# INT_CONN.net
KiCad netlist of a schematic drawn in Altium Designer
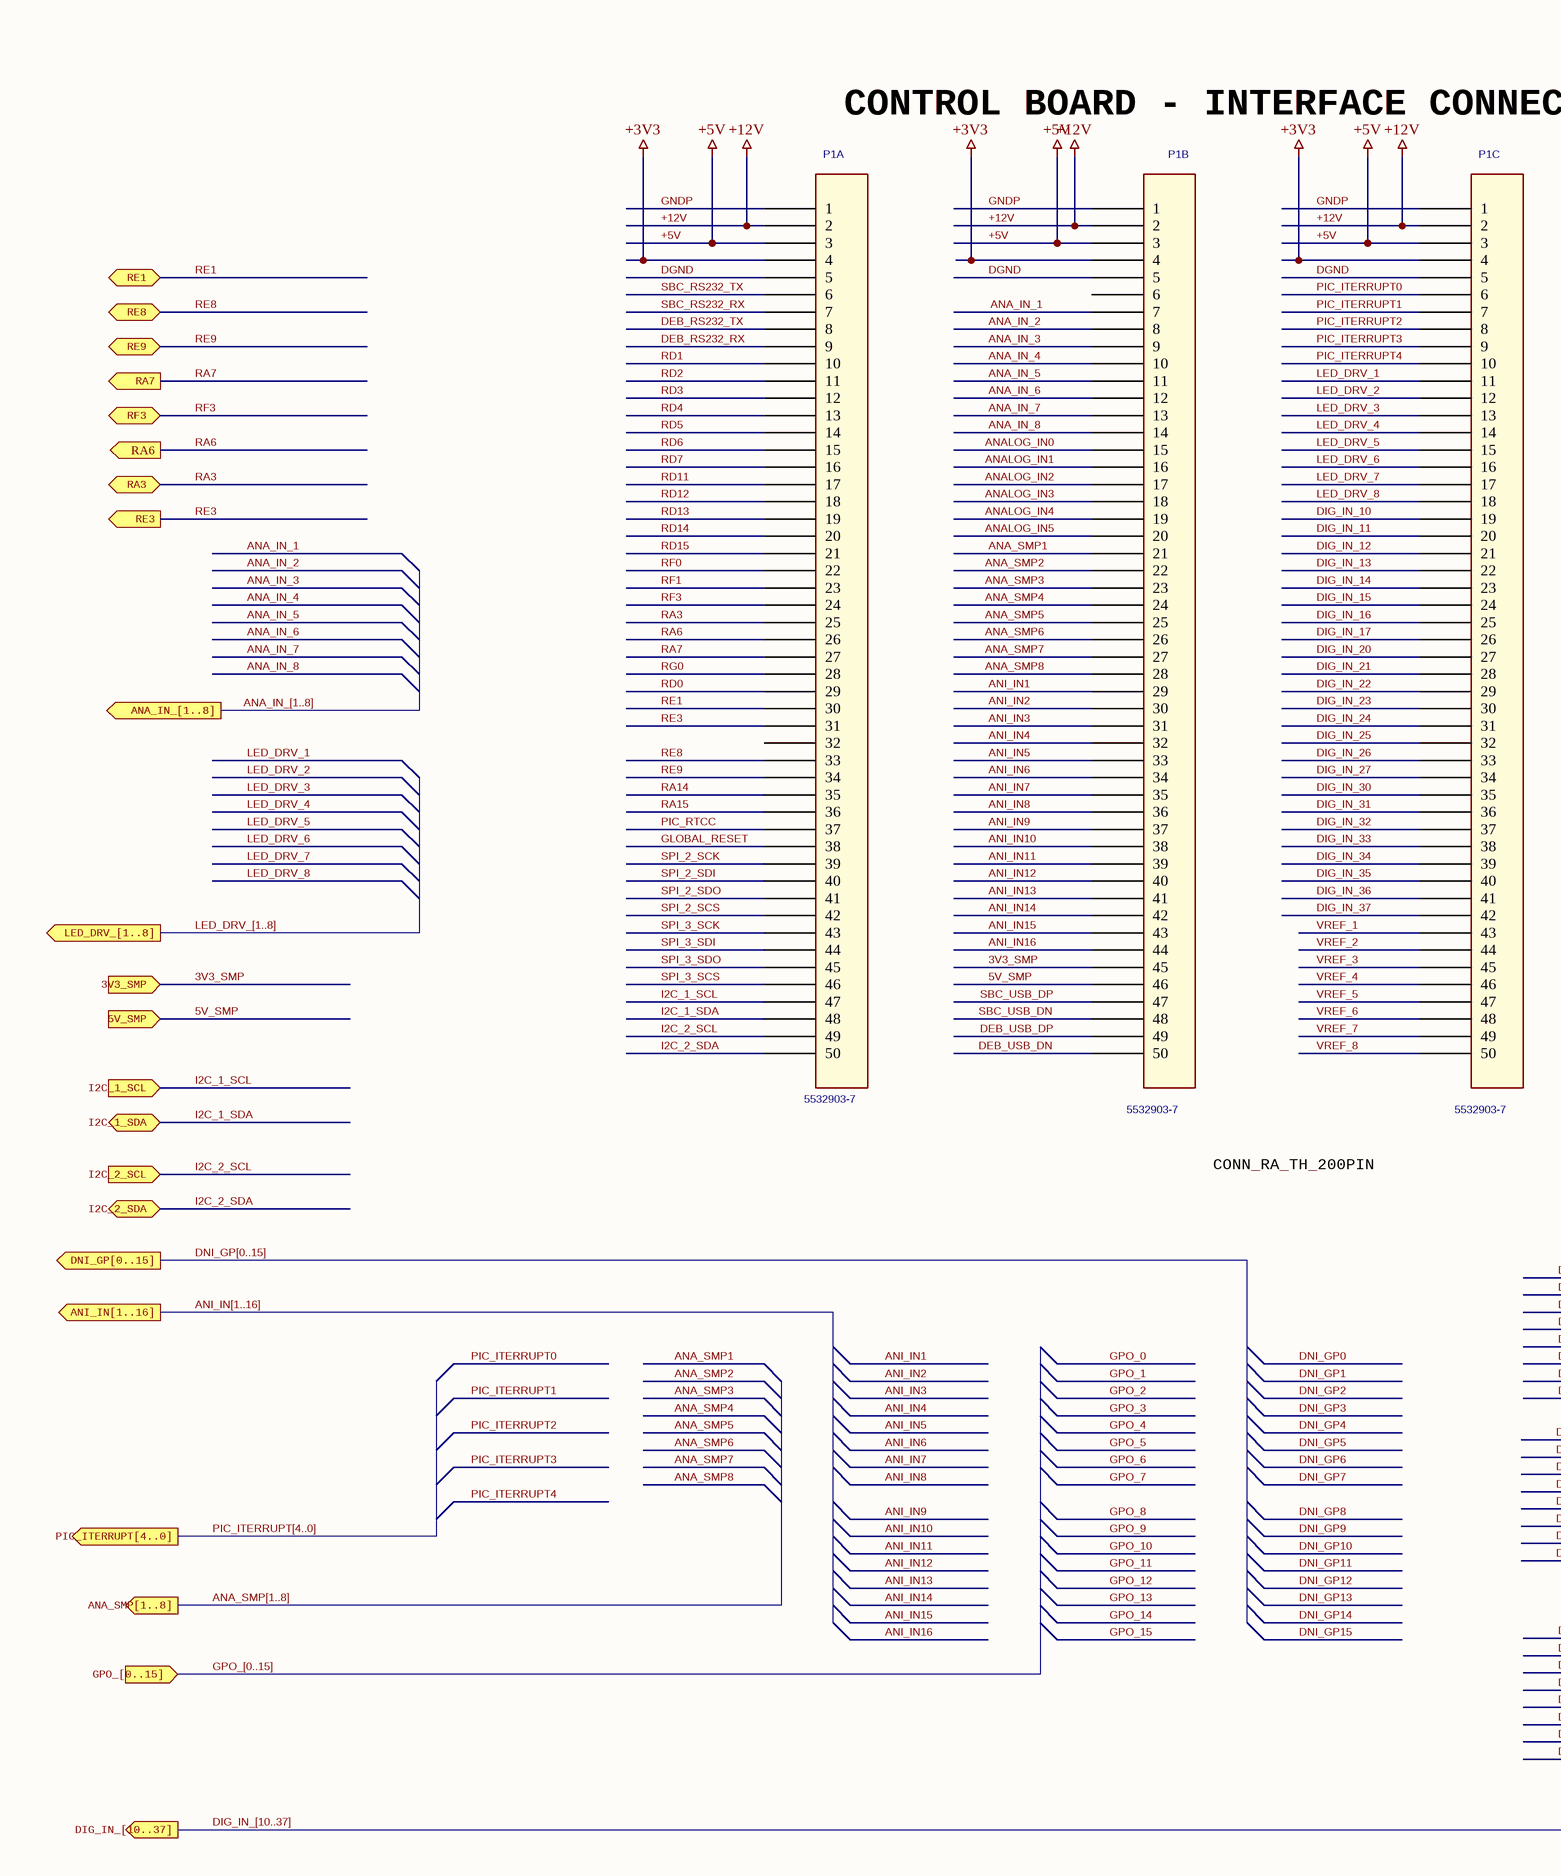
[diagram p0: INT_CONN.SchDoc, left]
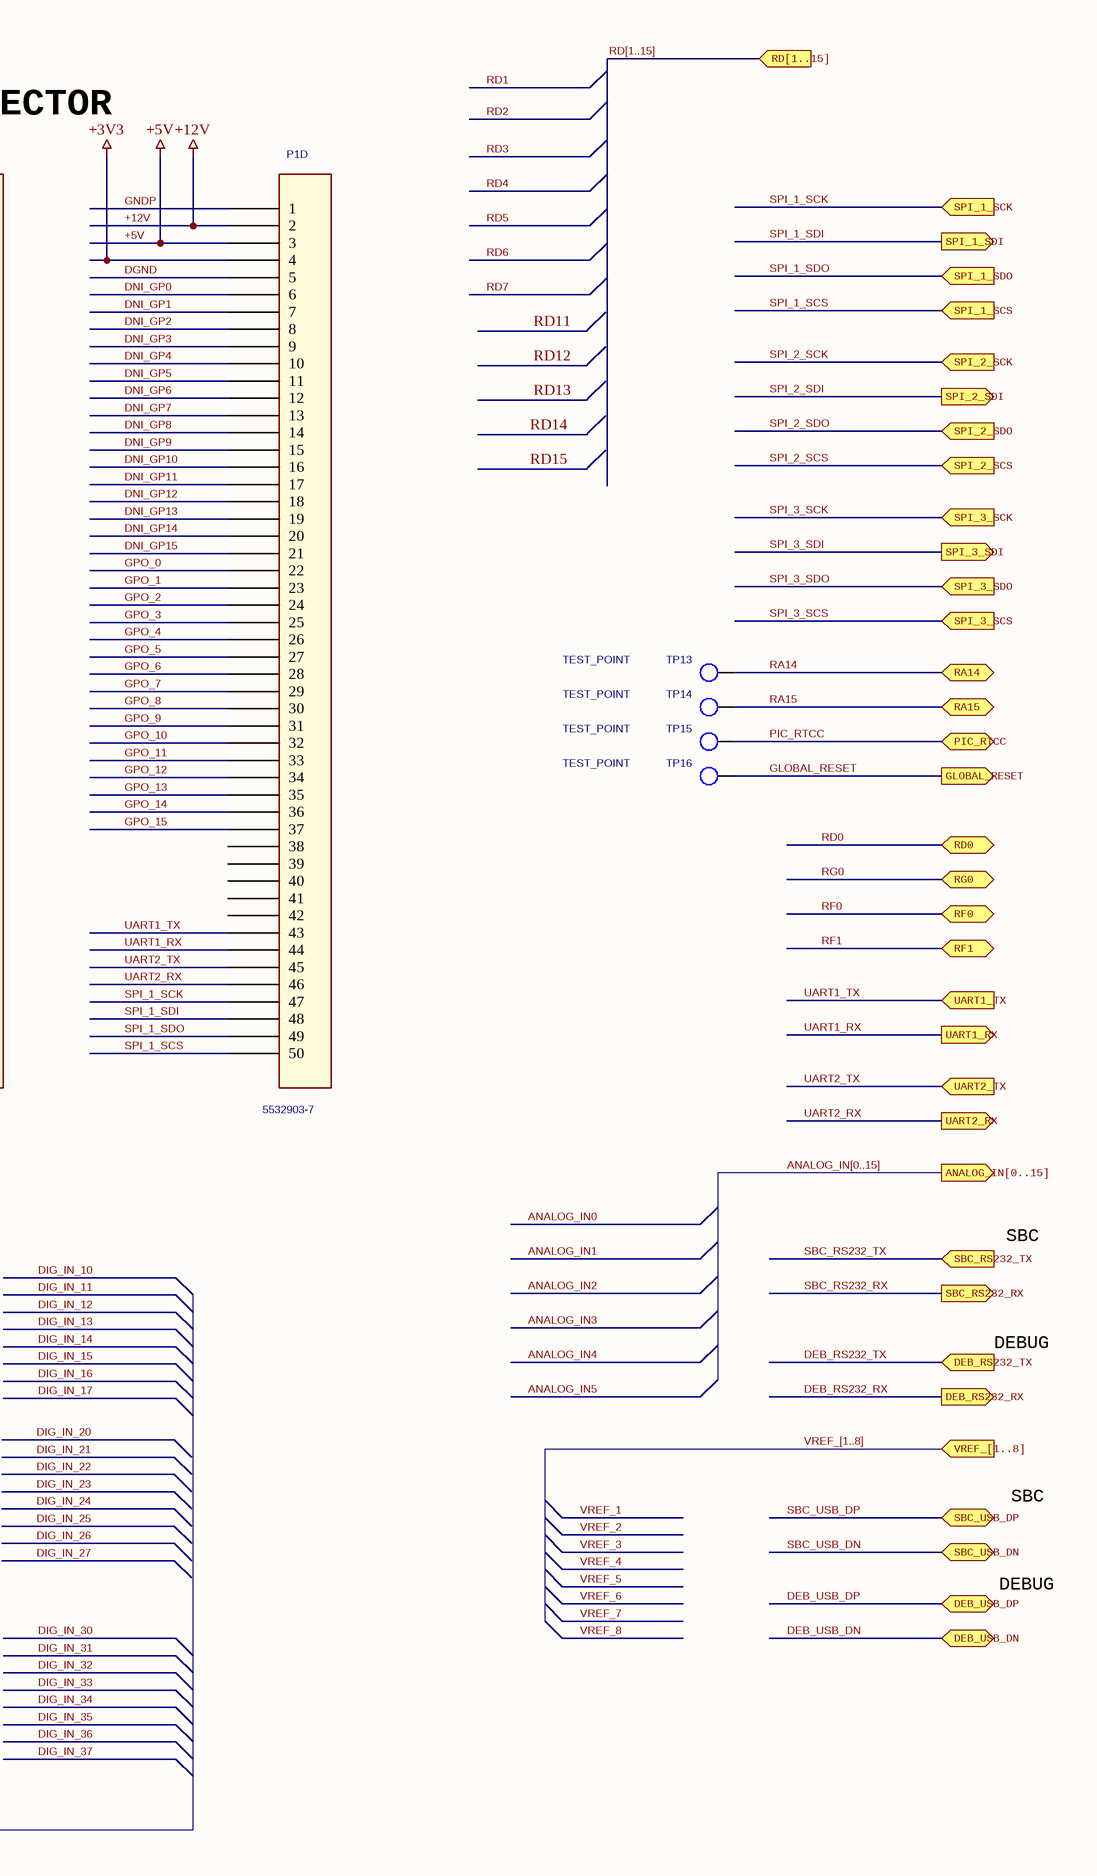
[diagram p1: INT_CONN.SchDoc, right]

(export (version "E")
  (design (tool "Eeschema 10.0.6"))
  (components
    (comp (ref "P1")
      (value "5532903-7")
      (footprint "TH_4X50_100mil")
      (libsource (lib "*") (part "CONN_RA_TH_200PIN"))
    )
    (comp (ref "TP13")
      (value "TEST_POINT")
      (footprint "TH_1mm")
      (libsource (lib "*") (part "T POINT R_Dup1"))
    )
    (comp (ref "TP14")
      (value "TEST_POINT")
      (footprint "TH_1mm")
      (libsource (lib "*") (part "T POINT R_Dup1"))
    )
    (comp (ref "TP15")
      (value "TEST_POINT")
      (footprint "TH_1mm")
      (libsource (lib "*") (part "T POINT R_Dup1"))
    )
    (comp (ref "TP16")
      (value "TEST_POINT")
      (footprint "TH_1mm")
      (libsource (lib "*") (part "T POINT R_Dup1"))
    )
  )
  (nets
    (net (code "18") (name "+3V3") (class "Default")
      (node (ref "P1") (pin "4A") (pinfunction "4_4A") (pintype "passive"))
      (node (ref "P1") (pin "4B") (pinfunction "4_4B") (pintype "passive"))
      (node (ref "P1") (pin "4C") (pinfunction "4_4C") (pintype "passive"))
      (node (ref "P1") (pin "4D") (pinfunction "4_4D") (pintype "passive"))
    )
    (net (code "19") (name "+5V") (class "Default")
      (node (ref "P1") (pin "3A") (pinfunction "3_3A") (pintype "passive"))
      (node (ref "P1") (pin "3B") (pinfunction "3_3B") (pintype "passive"))
      (node (ref "P1") (pin "3C") (pinfunction "3_3C") (pintype "passive"))
      (node (ref "P1") (pin "3D") (pinfunction "3_3D") (pintype "passive"))
    )
    (net (code "20") (name "+12V") (class "Default")
      (node (ref "P1") (pin "2A") (pinfunction "2_2A") (pintype "passive"))
      (node (ref "P1") (pin "2B") (pinfunction "2_2B") (pintype "passive"))
      (node (ref "P1") (pin "2C") (pinfunction "2_2C") (pintype "passive"))
      (node (ref "P1") (pin "2D") (pinfunction "2_2D") (pintype "passive"))
    )
    (net (code "21") (name "/3V3_SMP") (class "Default")
      (node (ref "P1") (pin "45B") (pinfunction "45_45B") (pintype "passive"))
    )
    (net (code "22") (name "/5V_SMP") (class "Default")
      (node (ref "P1") (pin "46B") (pinfunction "46_46B") (pintype "passive"))
    )
    (net (code "23") (name "/ANALOG_IN0") (class "Default")
      (node (ref "P1") (pin "15B") (pinfunction "15_15B") (pintype "passive"))
    )
    (net (code "24") (name "/ANALOG_IN1") (class "Default")
      (node (ref "P1") (pin "16B") (pinfunction "16_16B") (pintype "passive"))
    )
    (net (code "25") (name "/ANALOG_IN2") (class "Default")
      (node (ref "P1") (pin "17B") (pinfunction "17_17B") (pintype "passive"))
    )
    (net (code "26") (name "/ANALOG_IN3") (class "Default")
      (node (ref "P1") (pin "18B") (pinfunction "18_18B") (pintype "passive"))
    )
    (net (code "27") (name "/ANALOG_IN4") (class "Default")
      (node (ref "P1") (pin "19B") (pinfunction "19_19B") (pintype "passive"))
    )
    (net (code "28") (name "/ANALOG_IN5") (class "Default")
      (node (ref "P1") (pin "20B") (pinfunction "20_20B") (pintype "passive"))
    )
    (net (code "30") (name "/ANA_IN_1") (class "Default")
      (node (ref "P1") (pin "7B") (pinfunction "7_7B") (pintype "passive"))
    )
    (net (code "31") (name "/ANA_IN_2") (class "Default")
      (node (ref "P1") (pin "8B") (pinfunction "8_8B") (pintype "passive"))
    )
    (net (code "32") (name "/ANA_IN_3") (class "Default")
      (node (ref "P1") (pin "9B") (pinfunction "9_9B") (pintype "passive"))
    )
    (net (code "33") (name "/ANA_IN_4") (class "Default")
      (node (ref "P1") (pin "10B") (pinfunction "10_10B") (pintype "passive"))
    )
    (net (code "34") (name "/ANA_IN_5") (class "Default")
      (node (ref "P1") (pin "11B") (pinfunction "11_11B") (pintype "passive"))
    )
    (net (code "35") (name "/ANA_IN_6") (class "Default")
      (node (ref "P1") (pin "12B") (pinfunction "12_12B") (pintype "passive"))
    )
    (net (code "36") (name "/ANA_IN_7") (class "Default")
      (node (ref "P1") (pin "13B") (pinfunction "13_13B") (pintype "passive"))
    )
    (net (code "37") (name "/ANA_IN_8") (class "Default")
      (node (ref "P1") (pin "14B") (pinfunction "14_14B") (pintype "passive"))
    )
    (net (code "39") (name "/ANA_SMP1") (class "Default")
      (node (ref "P1") (pin "21B") (pinfunction "21_21B") (pintype "passive"))
    )
    (net (code "40") (name "/ANA_SMP2") (class "Default")
      (node (ref "P1") (pin "22B") (pinfunction "22_22B") (pintype "passive"))
    )
    (net (code "41") (name "/ANA_SMP3") (class "Default")
      (node (ref "P1") (pin "23B") (pinfunction "23_23B") (pintype "passive"))
    )
    (net (code "42") (name "/ANA_SMP4") (class "Default")
      (node (ref "P1") (pin "24B") (pinfunction "24_24B") (pintype "passive"))
    )
    (net (code "43") (name "/ANA_SMP5") (class "Default")
      (node (ref "P1") (pin "25B") (pinfunction "25_25B") (pintype "passive"))
    )
    (net (code "44") (name "/ANA_SMP6") (class "Default")
      (node (ref "P1") (pin "26B") (pinfunction "26_26B") (pintype "passive"))
    )
    (net (code "45") (name "/ANA_SMP7") (class "Default")
      (node (ref "P1") (pin "27B") (pinfunction "27_27B") (pintype "passive"))
    )
    (net (code "46") (name "/ANA_SMP8") (class "Default")
      (node (ref "P1") (pin "28B") (pinfunction "28_28B") (pintype "passive"))
    )
    (net (code "48") (name "/ANI_IN1") (class "Default")
      (node (ref "P1") (pin "29B") (pinfunction "29_29B") (pintype "passive"))
    )
    (net (code "49") (name "/ANI_IN2") (class "Default")
      (node (ref "P1") (pin "30B") (pinfunction "30_30B") (pintype "passive"))
    )
    (net (code "50") (name "/ANI_IN3") (class "Default")
      (node (ref "P1") (pin "31B") (pinfunction "31_31B") (pintype "passive"))
    )
    (net (code "51") (name "/ANI_IN4") (class "Default")
      (node (ref "P1") (pin "32B") (pinfunction "32_32B") (pintype "passive"))
    )
    (net (code "52") (name "/ANI_IN5") (class "Default")
      (node (ref "P1") (pin "33B") (pinfunction "33_33B") (pintype "passive"))
    )
    (net (code "53") (name "/ANI_IN6") (class "Default")
      (node (ref "P1") (pin "34B") (pinfunction "34_34B") (pintype "passive"))
    )
    (net (code "54") (name "/ANI_IN7") (class "Default")
      (node (ref "P1") (pin "35B") (pinfunction "35_35B") (pintype "passive"))
    )
    (net (code "55") (name "/ANI_IN8") (class "Default")
      (node (ref "P1") (pin "36B") (pinfunction "36_36B") (pintype "passive"))
    )
    (net (code "56") (name "/ANI_IN9") (class "Default")
      (node (ref "P1") (pin "37B") (pinfunction "37_37B") (pintype "passive"))
    )
    (net (code "57") (name "/ANI_IN10") (class "Default")
      (node (ref "P1") (pin "38B") (pinfunction "38_38B") (pintype "passive"))
    )
    (net (code "58") (name "/ANI_IN11") (class "Default")
      (node (ref "P1") (pin "39B") (pinfunction "39_39B") (pintype "passive"))
    )
    (net (code "59") (name "/ANI_IN12") (class "Default")
      (node (ref "P1") (pin "40B") (pinfunction "40_40B") (pintype "passive"))
    )
    (net (code "60") (name "/ANI_IN13") (class "Default")
      (node (ref "P1") (pin "41B") (pinfunction "41_41B") (pintype "passive"))
    )
    (net (code "61") (name "/ANI_IN14") (class "Default")
      (node (ref "P1") (pin "42B") (pinfunction "42_42B") (pintype "passive"))
    )
    (net (code "62") (name "/ANI_IN15") (class "Default")
      (node (ref "P1") (pin "43B") (pinfunction "43_43B") (pintype "passive"))
    )
    (net (code "63") (name "/ANI_IN16") (class "Default")
      (node (ref "P1") (pin "44B") (pinfunction "44_44B") (pintype "passive"))
    )
    (net (code "65") (name "/DEB_RS232_RX") (class "Default")
      (node (ref "P1") (pin "9A") (pinfunction "9_9A") (pintype "passive"))
    )
    (net (code "66") (name "/DEB_RS232_TX") (class "Default")
      (node (ref "P1") (pin "8A") (pinfunction "8_8A") (pintype "passive"))
    )
    (net (code "67") (name "/DEB_USB_DN") (class "Default")
      (node (ref "P1") (pin "50B") (pinfunction "50_50B") (pintype "passive"))
    )
    (net (code "68") (name "/DEB_USB_DP") (class "Default")
      (node (ref "P1") (pin "49B") (pinfunction "49_49B") (pintype "passive"))
    )
    (net (code "69") (name "/DGND") (class "Default")
      (node (ref "P1") (pin "5A") (pinfunction "5_5A") (pintype "passive"))
      (node (ref "P1") (pin "5B") (pinfunction "5_5B") (pintype "passive"))
      (node (ref "P1") (pin "5C") (pinfunction "5_5C") (pintype "passive"))
      (node (ref "P1") (pin "5D") (pinfunction "5_5D") (pintype "passive"))
    )
    (net (code "70") (name "/DIG_IN_10") (class "Default")
      (node (ref "P1") (pin "19C") (pinfunction "19_19C") (pintype "passive"))
    )
    (net (code "71") (name "/DIG_IN_11") (class "Default")
      (node (ref "P1") (pin "20C") (pinfunction "20_20C") (pintype "passive"))
    )
    (net (code "72") (name "/DIG_IN_12") (class "Default")
      (node (ref "P1") (pin "21C") (pinfunction "21_21C") (pintype "passive"))
    )
    (net (code "73") (name "/DIG_IN_13") (class "Default")
      (node (ref "P1") (pin "22C") (pinfunction "22_22C") (pintype "passive"))
    )
    (net (code "74") (name "/DIG_IN_14") (class "Default")
      (node (ref "P1") (pin "23C") (pinfunction "23_23C") (pintype "passive"))
    )
    (net (code "75") (name "/DIG_IN_15") (class "Default")
      (node (ref "P1") (pin "24C") (pinfunction "24_24C") (pintype "passive"))
    )
    (net (code "76") (name "/DIG_IN_16") (class "Default")
      (node (ref "P1") (pin "25C") (pinfunction "25_25C") (pintype "passive"))
    )
    (net (code "77") (name "/DIG_IN_17") (class "Default")
      (node (ref "P1") (pin "26C") (pinfunction "26_26C") (pintype "passive"))
    )
    (net (code "78") (name "/DIG_IN_20") (class "Default")
      (node (ref "P1") (pin "27C") (pinfunction "27_27C") (pintype "passive"))
    )
    (net (code "79") (name "/DIG_IN_21") (class "Default")
      (node (ref "P1") (pin "28C") (pinfunction "28_28C") (pintype "passive"))
    )
    (net (code "80") (name "/DIG_IN_22") (class "Default")
      (node (ref "P1") (pin "29C") (pinfunction "29_29C") (pintype "passive"))
    )
    (net (code "81") (name "/DIG_IN_23") (class "Default")
      (node (ref "P1") (pin "30C") (pinfunction "30_30C") (pintype "passive"))
    )
    (net (code "82") (name "/DIG_IN_24") (class "Default")
      (node (ref "P1") (pin "31C") (pinfunction "31_31C") (pintype "passive"))
    )
    (net (code "83") (name "/DIG_IN_25") (class "Default")
      (node (ref "P1") (pin "32C") (pinfunction "32_32C") (pintype "passive"))
    )
    (net (code "84") (name "/DIG_IN_26") (class "Default")
      (node (ref "P1") (pin "33C") (pinfunction "33_33C") (pintype "passive"))
    )
    (net (code "85") (name "/DIG_IN_27") (class "Default")
      (node (ref "P1") (pin "34C") (pinfunction "34_34C") (pintype "passive"))
    )
    (net (code "86") (name "/DIG_IN_30") (class "Default")
      (node (ref "P1") (pin "35C") (pinfunction "35_35C") (pintype "passive"))
    )
    (net (code "87") (name "/DIG_IN_31") (class "Default")
      (node (ref "P1") (pin "36C") (pinfunction "36_36C") (pintype "passive"))
    )
    (net (code "88") (name "/DIG_IN_32") (class "Default")
      (node (ref "P1") (pin "37C") (pinfunction "37_37C") (pintype "passive"))
    )
    (net (code "89") (name "/DIG_IN_33") (class "Default")
      (node (ref "P1") (pin "38C") (pinfunction "38_38C") (pintype "passive"))
    )
    (net (code "90") (name "/DIG_IN_34") (class "Default")
      (node (ref "P1") (pin "39C") (pinfunction "39_39C") (pintype "passive"))
    )
    (net (code "91") (name "/DIG_IN_35") (class "Default")
      (node (ref "P1") (pin "40C") (pinfunction "40_40C") (pintype "passive"))
    )
    (net (code "92") (name "/DIG_IN_36") (class "Default")
      (node (ref "P1") (pin "41C") (pinfunction "41_41C") (pintype "passive"))
    )
    (net (code "93") (name "/DIG_IN_37") (class "Default")
      (node (ref "P1") (pin "42C") (pinfunction "42_42C") (pintype "passive"))
    )
    (net (code "95") (name "/DNI_GP0") (class "Default")
      (node (ref "P1") (pin "6D") (pinfunction "6_6D") (pintype "passive"))
    )
    (net (code "96") (name "/DNI_GP1") (class "Default")
      (node (ref "P1") (pin "7D") (pinfunction "7_7D") (pintype "passive"))
    )
    (net (code "97") (name "/DNI_GP2") (class "Default")
      (node (ref "P1") (pin "8D") (pinfunction "8_8D") (pintype "passive"))
    )
    (net (code "98") (name "/DNI_GP3") (class "Default")
      (node (ref "P1") (pin "9D") (pinfunction "9_9D") (pintype "passive"))
    )
    (net (code "99") (name "/DNI_GP4") (class "Default")
      (node (ref "P1") (pin "10D") (pinfunction "10_10D") (pintype "passive"))
    )
    (net (code "100") (name "/DNI_GP5") (class "Default")
      (node (ref "P1") (pin "11D") (pinfunction "11_11D") (pintype "passive"))
    )
    (net (code "101") (name "/DNI_GP6") (class "Default")
      (node (ref "P1") (pin "12D") (pinfunction "12_12D") (pintype "passive"))
    )
    (net (code "102") (name "/DNI_GP7") (class "Default")
      (node (ref "P1") (pin "13D") (pinfunction "13_13D") (pintype "passive"))
    )
    (net (code "103") (name "/DNI_GP8") (class "Default")
      (node (ref "P1") (pin "14D") (pinfunction "14_14D") (pintype "passive"))
    )
    (net (code "104") (name "/DNI_GP9") (class "Default")
      (node (ref "P1") (pin "15D") (pinfunction "15_15D") (pintype "passive"))
    )
    (net (code "105") (name "/DNI_GP10") (class "Default")
      (node (ref "P1") (pin "16D") (pinfunction "16_16D") (pintype "passive"))
    )
    (net (code "106") (name "/DNI_GP11") (class "Default")
      (node (ref "P1") (pin "17D") (pinfunction "17_17D") (pintype "passive"))
    )
    (net (code "107") (name "/DNI_GP12") (class "Default")
      (node (ref "P1") (pin "18D") (pinfunction "18_18D") (pintype "passive"))
    )
    (net (code "108") (name "/DNI_GP13") (class "Default")
      (node (ref "P1") (pin "19D") (pinfunction "19_19D") (pintype "passive"))
    )
    (net (code "109") (name "/DNI_GP14") (class "Default")
      (node (ref "P1") (pin "20D") (pinfunction "20_20D") (pintype "passive"))
    )
    (net (code "110") (name "/DNI_GP15") (class "Default")
      (node (ref "P1") (pin "21D") (pinfunction "21_21D") (pintype "passive"))
    )
    (net (code "112") (name "/GLOBAL_RESET") (class "Default")
      (node (ref "P1") (pin "38A") (pinfunction "38_38A") (pintype "passive"))
      (node (ref "TP16") (pin "1") (pinfunction "TP_1") (pintype "passive"))
    )
    (net (code "113") (name "/GNDP") (class "Default")
      (node (ref "P1") (pin "1A") (pinfunction "1_1A") (pintype "passive"))
      (node (ref "P1") (pin "1B") (pinfunction "1_1B") (pintype "passive"))
      (node (ref "P1") (pin "1C") (pinfunction "1_1C") (pintype "passive"))
      (node (ref "P1") (pin "1D") (pinfunction "1_1D") (pintype "passive"))
    )
    (net (code "114") (name "/GPO_0") (class "Default")
      (node (ref "P1") (pin "22D") (pinfunction "22_22D") (pintype "passive"))
    )
    (net (code "115") (name "/GPO_1") (class "Default")
      (node (ref "P1") (pin "23D") (pinfunction "23_23D") (pintype "passive"))
    )
    (net (code "116") (name "/GPO_2") (class "Default")
      (node (ref "P1") (pin "24D") (pinfunction "24_24D") (pintype "passive"))
    )
    (net (code "117") (name "/GPO_3") (class "Default")
      (node (ref "P1") (pin "25D") (pinfunction "25_25D") (pintype "passive"))
    )
    (net (code "118") (name "/GPO_4") (class "Default")
      (node (ref "P1") (pin "26D") (pinfunction "26_26D") (pintype "passive"))
    )
    (net (code "119") (name "/GPO_5") (class "Default")
      (node (ref "P1") (pin "27D") (pinfunction "27_27D") (pintype "passive"))
    )
    (net (code "120") (name "/GPO_6") (class "Default")
      (node (ref "P1") (pin "28D") (pinfunction "28_28D") (pintype "passive"))
    )
    (net (code "121") (name "/GPO_7") (class "Default")
      (node (ref "P1") (pin "29D") (pinfunction "29_29D") (pintype "passive"))
    )
    (net (code "122") (name "/GPO_8") (class "Default")
      (node (ref "P1") (pin "30D") (pinfunction "30_30D") (pintype "passive"))
    )
    (net (code "123") (name "/GPO_9") (class "Default")
      (node (ref "P1") (pin "31D") (pinfunction "31_31D") (pintype "passive"))
    )
    (net (code "124") (name "/GPO_10") (class "Default")
      (node (ref "P1") (pin "32D") (pinfunction "32_32D") (pintype "passive"))
    )
    (net (code "125") (name "/GPO_11") (class "Default")
      (node (ref "P1") (pin "33D") (pinfunction "33_33D") (pintype "passive"))
    )
    (net (code "126") (name "/GPO_12") (class "Default")
      (node (ref "P1") (pin "34D") (pinfunction "34_34D") (pintype "passive"))
    )
    (net (code "127") (name "/GPO_13") (class "Default")
      (node (ref "P1") (pin "35D") (pinfunction "35_35D") (pintype "passive"))
    )
    (net (code "128") (name "/GPO_14") (class "Default")
      (node (ref "P1") (pin "36D") (pinfunction "36_36D") (pintype "passive"))
    )
    (net (code "129") (name "/GPO_15") (class "Default")
      (node (ref "P1") (pin "37D") (pinfunction "37_37D") (pintype "passive"))
    )
    (net (code "131") (name "/I2C_1_SCL") (class "Default")
      (node (ref "P1") (pin "47A") (pinfunction "47_47A") (pintype "passive"))
    )
    (net (code "132") (name "/I2C_1_SDA") (class "Default")
      (node (ref "P1") (pin "48A") (pinfunction "48_48A") (pintype "passive"))
    )
    (net (code "133") (name "/I2C_2_SCL") (class "Default")
      (node (ref "P1") (pin "49A") (pinfunction "49_49A") (pintype "passive"))
    )
    (net (code "134") (name "/I2C_2_SDA") (class "Default")
      (node (ref "P1") (pin "50A") (pinfunction "50_50A") (pintype "passive"))
    )
    (net (code "135") (name "/LED_DRV_1") (class "Default")
      (node (ref "P1") (pin "11C") (pinfunction "11_11C") (pintype "passive"))
    )
    (net (code "136") (name "/LED_DRV_2") (class "Default")
      (node (ref "P1") (pin "12C") (pinfunction "12_12C") (pintype "passive"))
    )
    (net (code "137") (name "/LED_DRV_3") (class "Default")
      (node (ref "P1") (pin "13C") (pinfunction "13_13C") (pintype "passive"))
    )
    (net (code "138") (name "/LED_DRV_4") (class "Default")
      (node (ref "P1") (pin "14C") (pinfunction "14_14C") (pintype "passive"))
    )
    (net (code "139") (name "/LED_DRV_5") (class "Default")
      (node (ref "P1") (pin "15C") (pinfunction "15_15C") (pintype "passive"))
    )
    (net (code "140") (name "/LED_DRV_6") (class "Default")
      (node (ref "P1") (pin "16C") (pinfunction "16_16C") (pintype "passive"))
    )
    (net (code "141") (name "/LED_DRV_7") (class "Default")
      (node (ref "P1") (pin "17C") (pinfunction "17_17C") (pintype "passive"))
    )
    (net (code "142") (name "/LED_DRV_8") (class "Default")
      (node (ref "P1") (pin "18C") (pinfunction "18_18C") (pintype "passive"))
    )
    (net (code "144") (name "/PIC_ITERRUPT0") (class "Default")
      (node (ref "P1") (pin "6C") (pinfunction "6_6C") (pintype "passive"))
    )
    (net (code "145") (name "/PIC_ITERRUPT1") (class "Default")
      (node (ref "P1") (pin "7C") (pinfunction "7_7C") (pintype "passive"))
    )
    (net (code "146") (name "/PIC_ITERRUPT2") (class "Default")
      (node (ref "P1") (pin "8C") (pinfunction "8_8C") (pintype "passive"))
    )
    (net (code "147") (name "/PIC_ITERRUPT3") (class "Default")
      (node (ref "P1") (pin "9C") (pinfunction "9_9C") (pintype "passive"))
    )
    (net (code "148") (name "/PIC_ITERRUPT4") (class "Default")
      (node (ref "P1") (pin "10C") (pinfunction "10_10C") (pintype "passive"))
    )
    (net (code "150") (name "/PIC_RTCC") (class "Default")
      (node (ref "P1") (pin "37A") (pinfunction "37_37A") (pintype "passive"))
      (node (ref "TP15") (pin "1") (pinfunction "TP_1") (pintype "passive"))
    )
    (net (code "151") (name "/RA3") (class "Default")
      (node (ref "P1") (pin "25A") (pinfunction "25_25A") (pintype "passive"))
    )
    (net (code "152") (name "/RA6") (class "Default")
      (node (ref "P1") (pin "26A") (pinfunction "26_26A") (pintype "passive"))
    )
    (net (code "153") (name "/RA7") (class "Default")
      (node (ref "P1") (pin "27A") (pinfunction "27_27A") (pintype "passive"))
    )
    (net (code "154") (name "/RA14") (class "Default")
      (node (ref "P1") (pin "35A") (pinfunction "35_35A") (pintype "passive"))
      (node (ref "TP13") (pin "1") (pinfunction "TP_1") (pintype "passive"))
    )
    (net (code "155") (name "/RA15") (class "Default")
      (node (ref "P1") (pin "36A") (pinfunction "36_36A") (pintype "passive"))
      (node (ref "TP14") (pin "1") (pinfunction "TP_1") (pintype "passive"))
    )
    (net (code "156") (name "/RD0") (class "Default")
      (node (ref "P1") (pin "29A") (pinfunction "29_29A") (pintype "passive"))
    )
    (net (code "157") (name "/RD1") (class "Default")
      (node (ref "P1") (pin "10A") (pinfunction "10_10A") (pintype "passive"))
    )
    (net (code "158") (name "/RD2") (class "Default")
      (node (ref "P1") (pin "11A") (pinfunction "11_11A") (pintype "passive"))
    )
    (net (code "159") (name "/RD3") (class "Default")
      (node (ref "P1") (pin "12A") (pinfunction "12_12A") (pintype "passive"))
    )
    (net (code "160") (name "/RD4") (class "Default")
      (node (ref "P1") (pin "13A") (pinfunction "13_13A") (pintype "passive"))
    )
    (net (code "161") (name "/RD5") (class "Default")
      (node (ref "P1") (pin "14A") (pinfunction "14_14A") (pintype "passive"))
    )
    (net (code "162") (name "/RD6") (class "Default")
      (node (ref "P1") (pin "15A") (pinfunction "15_15A") (pintype "passive"))
    )
    (net (code "163") (name "/RD7") (class "Default")
      (node (ref "P1") (pin "16A") (pinfunction "16_16A") (pintype "passive"))
    )
    (net (code "164") (name "/RD11") (class "Default")
      (node (ref "P1") (pin "17A") (pinfunction "17_17A") (pintype "passive"))
    )
    (net (code "165") (name "/RD12") (class "Default")
      (node (ref "P1") (pin "18A") (pinfunction "18_18A") (pintype "passive"))
    )
    (net (code "166") (name "/RD13") (class "Default")
      (node (ref "P1") (pin "19A") (pinfunction "19_19A") (pintype "passive"))
    )
    (net (code "167") (name "/RD14") (class "Default")
      (node (ref "P1") (pin "20A") (pinfunction "20_20A") (pintype "passive"))
    )
    (net (code "168") (name "/RD15") (class "Default")
      (node (ref "P1") (pin "21A") (pinfunction "21_21A") (pintype "passive"))
    )
    (net (code "170") (name "/RE1") (class "Default")
      (node (ref "P1") (pin "30A") (pinfunction "30_30A") (pintype "passive"))
    )
    (net (code "171") (name "/RE3") (class "Default")
      (node (ref "P1") (pin "31A") (pinfunction "31_31A") (pintype "passive"))
    )
    (net (code "172") (name "/RE8") (class "Default")
      (node (ref "P1") (pin "33A") (pinfunction "33_33A") (pintype "passive"))
    )
    (net (code "173") (name "/RE9") (class "Default")
      (node (ref "P1") (pin "34A") (pinfunction "34_34A") (pintype "passive"))
    )
    (net (code "174") (name "/RF0") (class "Default")
      (node (ref "P1") (pin "22A") (pinfunction "22_22A") (pintype "passive"))
    )
    (net (code "175") (name "/RF1") (class "Default")
      (node (ref "P1") (pin "23A") (pinfunction "23_23A") (pintype "passive"))
    )
    (net (code "176") (name "/RF3") (class "Default")
      (node (ref "P1") (pin "24A") (pinfunction "24_24A") (pintype "passive"))
    )
    (net (code "177") (name "/RG0") (class "Default")
      (node (ref "P1") (pin "28A") (pinfunction "28_28A") (pintype "passive"))
    )
    (net (code "178") (name "/SBC_RS232_RX") (class "Default")
      (node (ref "P1") (pin "7A") (pinfunction "7_7A") (pintype "passive"))
    )
    (net (code "179") (name "/SBC_RS232_TX") (class "Default")
      (node (ref "P1") (pin "6A") (pinfunction "6_6A") (pintype "passive"))
    )
    (net (code "180") (name "/SBC_USB_DN") (class "Default")
      (node (ref "P1") (pin "48B") (pinfunction "48_48B") (pintype "passive"))
    )
    (net (code "181") (name "/SBC_USB_DP") (class "Default")
      (node (ref "P1") (pin "47B") (pinfunction "47_47B") (pintype "passive"))
    )
    (net (code "182") (name "/SPI_1_SCK") (class "Default")
      (node (ref "P1") (pin "47D") (pinfunction "47_47D") (pintype "passive"))
    )
    (net (code "183") (name "/SPI_1_SCS") (class "Default")
      (node (ref "P1") (pin "50D") (pinfunction "50_50D") (pintype "passive"))
    )
    (net (code "184") (name "/SPI_1_SDI") (class "Default")
      (node (ref "P1") (pin "48D") (pinfunction "48_48D") (pintype "passive"))
    )
    (net (code "185") (name "/SPI_1_SDO") (class "Default")
      (node (ref "P1") (pin "49D") (pinfunction "49_49D") (pintype "passive"))
    )
    (net (code "186") (name "/SPI_2_SCK") (class "Default")
      (node (ref "P1") (pin "39A") (pinfunction "39_39A") (pintype "passive"))
    )
    (net (code "187") (name "/SPI_2_SCS") (class "Default")
      (node (ref "P1") (pin "42A") (pinfunction "42_42A") (pintype "passive"))
    )
    (net (code "188") (name "/SPI_2_SDI") (class "Default")
      (node (ref "P1") (pin "40A") (pinfunction "40_40A") (pintype "passive"))
    )
    (net (code "189") (name "/SPI_2_SDO") (class "Default")
      (node (ref "P1") (pin "41A") (pinfunction "41_41A") (pintype "passive"))
    )
    (net (code "190") (name "/SPI_3_SCK") (class "Default")
      (node (ref "P1") (pin "43A") (pinfunction "43_43A") (pintype "passive"))
    )
    (net (code "191") (name "/SPI_3_SCS") (class "Default")
      (node (ref "P1") (pin "46A") (pinfunction "46_46A") (pintype "passive"))
    )
    (net (code "192") (name "/SPI_3_SDI") (class "Default")
      (node (ref "P1") (pin "44A") (pinfunction "44_44A") (pintype "passive"))
    )
    (net (code "193") (name "/SPI_3_SDO") (class "Default")
      (node (ref "P1") (pin "45A") (pinfunction "45_45A") (pintype "passive"))
    )
    (net (code "194") (name "/UART1_RX") (class "Default")
      (node (ref "P1") (pin "44D") (pinfunction "44_44D") (pintype "passive"))
    )
    (net (code "195") (name "/UART1_TX") (class "Default")
      (node (ref "P1") (pin "43D") (pinfunction "43_43D") (pintype "passive"))
    )
    (net (code "196") (name "/UART2_RX") (class "Default")
      (node (ref "P1") (pin "46D") (pinfunction "46_46D") (pintype "passive"))
    )
    (net (code "197") (name "/UART2_TX") (class "Default")
      (node (ref "P1") (pin "45D") (pinfunction "45_45D") (pintype "passive"))
    )
    (net (code "198") (name "/VREF_1") (class "Default")
      (node (ref "P1") (pin "43C") (pinfunction "43_43C") (pintype "passive"))
    )
    (net (code "199") (name "/VREF_2") (class "Default")
      (node (ref "P1") (pin "44C") (pinfunction "44_44C") (pintype "passive"))
    )
    (net (code "200") (name "/VREF_3") (class "Default")
      (node (ref "P1") (pin "45C") (pinfunction "45_45C") (pintype "passive"))
    )
    (net (code "201") (name "/VREF_4") (class "Default")
      (node (ref "P1") (pin "46C") (pinfunction "46_46C") (pintype "passive"))
    )
    (net (code "202") (name "/VREF_5") (class "Default")
      (node (ref "P1") (pin "47C") (pinfunction "47_47C") (pintype "passive"))
    )
    (net (code "203") (name "/VREF_6") (class "Default")
      (node (ref "P1") (pin "48C") (pinfunction "48_48C") (pintype "passive"))
    )
    (net (code "204") (name "/VREF_7") (class "Default")
      (node (ref "P1") (pin "49C") (pinfunction "49_49C") (pintype "passive"))
    )
    (net (code "205") (name "/VREF_8") (class "Default")
      (node (ref "P1") (pin "50C") (pinfunction "50_50C") (pintype "passive"))
    )
    (net (code "207") (name "unconnected-(P1A-32-Pad32A)") (class "Default")
      (node (ref "P1") (pin "32A") (pinfunction "32_32A") (pintype "passive"))
    )
    (net (code "208") (name "unconnected-(P1B-6-Pad6B)") (class "Default")
      (node (ref "P1") (pin "6B") (pinfunction "6_6B") (pintype "passive"))
    )
    (net (code "209") (name "unconnected-(P1D-38-Pad38D)") (class "Default")
      (node (ref "P1") (pin "38D") (pinfunction "38_38D") (pintype "passive"))
    )
    (net (code "210") (name "unconnected-(P1D-39-Pad39D)") (class "Default")
      (node (ref "P1") (pin "39D") (pinfunction "39_39D") (pintype "passive"))
    )
    (net (code "211") (name "unconnected-(P1D-40-Pad40D)") (class "Default")
      (node (ref "P1") (pin "40D") (pinfunction "40_40D") (pintype "passive"))
    )
    (net (code "212") (name "unconnected-(P1D-41-Pad41D)") (class "Default")
      (node (ref "P1") (pin "41D") (pinfunction "41_41D") (pintype "passive"))
    )
    (net (code "213") (name "unconnected-(P1D-42-Pad42D)") (class "Default")
      (node (ref "P1") (pin "42D") (pinfunction "42_42D") (pintype "passive"))
    )
  )
)
